# schematic.net
KiCad netlist of a schematic drawn in Altium Designer
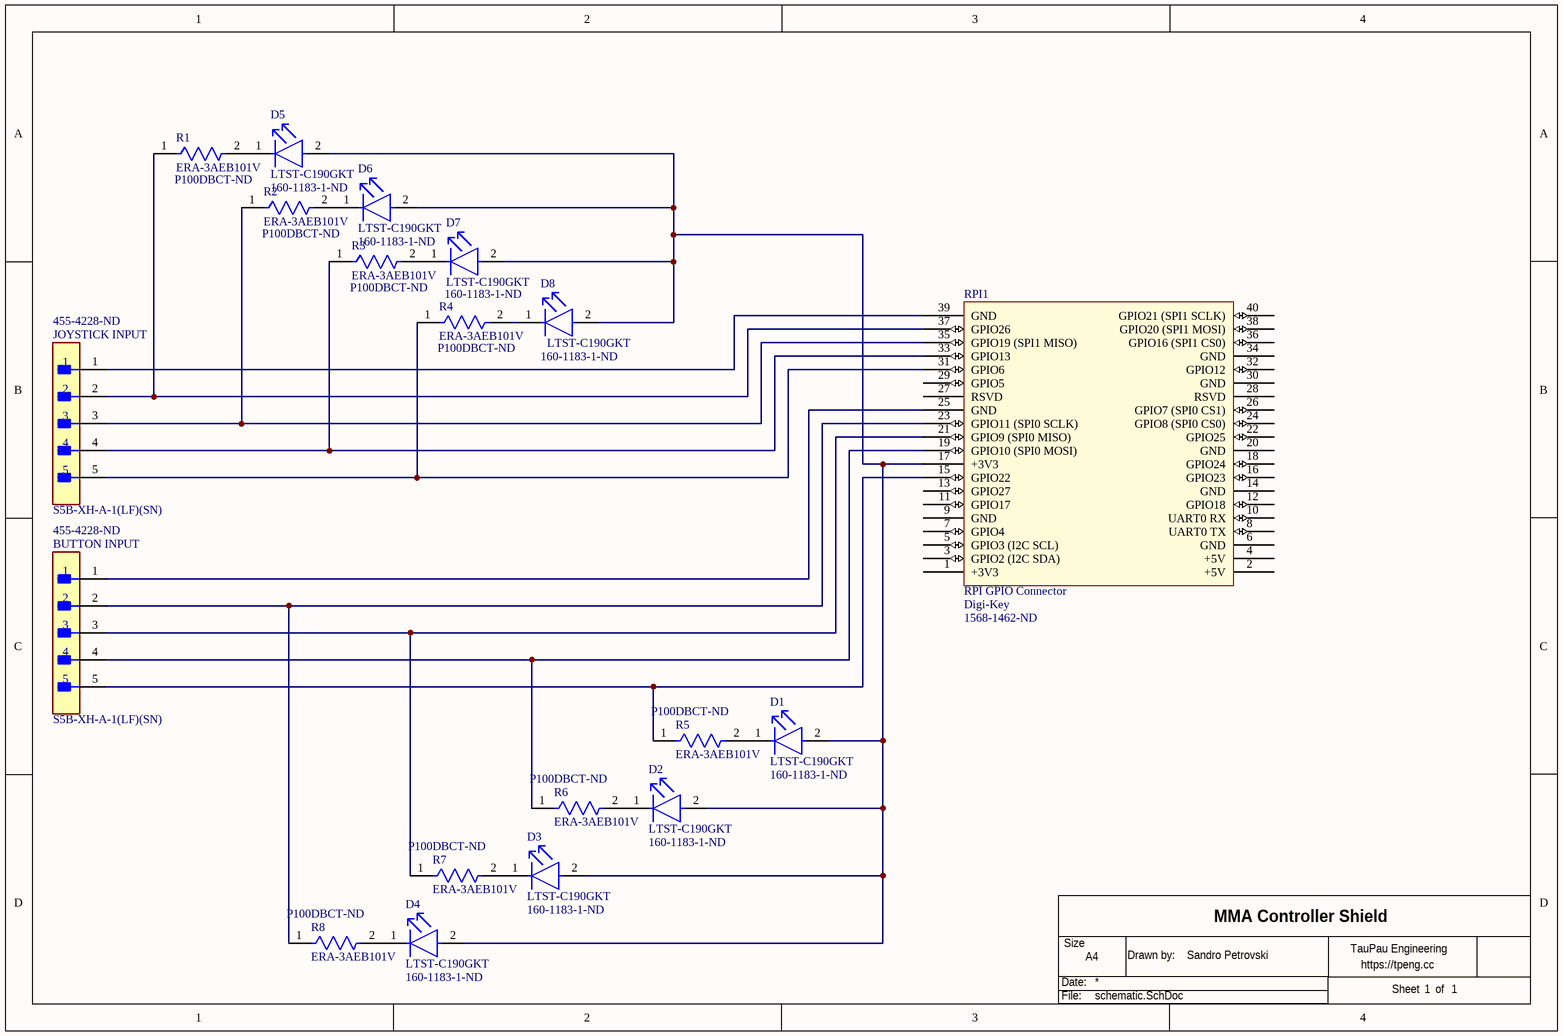
[diagram p0: schematic.SchDoc]

(export (version "E")
  (design (tool "Eeschema 10.0.6"))
  (components
    (comp (ref "*")
      (value "TPE Title Block")
      (description "TPE Title block")
      (libsource (lib "title_block") (part "TPE Title Block"))
    )
    (comp (ref "BUTTON INPUT")
      (value "S5B-XH-A-1(LF)(SN)")
      (footprint "FP-S5B-XH-A-1_LF_SN-MFG")
      (description "CONN HEADER R/A 5POS 2.5MM")
      (fields (field (name "SUPPLIER PART NUMBER 1") "455-4228-ND") (field (name "MANUFACTURER") "JST"))
      (libsource (lib "Altium Content Vault") (part "bf93c07fd2649a848d0ec8585582aab"))
    )
    (comp (ref "D1")
      (value "LTST-C190GKT")
      (footprint "FP-LTST-C190GKT-MFG")
      (description "LED GREEN CLEAR CHIP SMD")
      (fields
        (field (name "VOLTAGE") "2V")
        (field (name "SUPPLIER PART NUMBER 1") "160-1183-1-ND")
        (field (name "MANUFACTURER") "Vishay Lite-On")
      )
      (libsource (lib "Altium Content Vault") (part "8706943c75ba83719d021d2fdc84c58"))
    )
    (comp (ref "D2")
      (value "LTST-C190GKT")
      (footprint "FP-LTST-C190GKT-MFG")
      (description "LED GREEN CLEAR CHIP SMD")
      (fields
        (field (name "VOLTAGE") "2V")
        (field (name "SUPPLIER PART NUMBER 1") "160-1183-1-ND")
        (field (name "MANUFACTURER") "Vishay Lite-On")
      )
      (libsource (lib "Altium Content Vault") (part "8706943c75ba83719d021d2fdc84c58"))
    )
    (comp (ref "D3")
      (value "LTST-C190GKT")
      (footprint "FP-LTST-C190GKT-MFG")
      (description "LED GREEN CLEAR CHIP SMD")
      (fields
        (field (name "VOLTAGE") "2V")
        (field (name "SUPPLIER PART NUMBER 1") "160-1183-1-ND")
        (field (name "MANUFACTURER") "Vishay Lite-On")
      )
      (libsource (lib "Altium Content Vault") (part "8706943c75ba83719d021d2fdc84c58"))
    )
    (comp (ref "D4")
      (value "LTST-C190GKT")
      (footprint "FP-LTST-C190GKT-MFG")
      (description "LED GREEN CLEAR CHIP SMD")
      (fields
        (field (name "VOLTAGE") "2V")
        (field (name "SUPPLIER PART NUMBER 1") "160-1183-1-ND")
        (field (name "MANUFACTURER") "Vishay Lite-On")
      )
      (libsource (lib "Altium Content Vault") (part "8706943c75ba83719d021d2fdc84c58"))
    )
    (comp (ref "D5")
      (value "LTST-C190GKT")
      (footprint "FP-LTST-C190GKT-MFG")
      (description "LED GREEN CLEAR CHIP SMD")
      (fields
        (field (name "VOLTAGE") "2V")
        (field (name "SUPPLIER PART NUMBER 1") "160-1183-1-ND")
        (field (name "MANUFACTURER") "Vishay Lite-On")
      )
      (libsource (lib "Altium Content Vault") (part "8706943c75ba83719d021d2fdc84c58"))
    )
    (comp (ref "D6")
      (value "LTST-C190GKT")
      (footprint "FP-LTST-C190GKT-MFG")
      (description "LED GREEN CLEAR CHIP SMD")
      (fields
        (field (name "VOLTAGE") "2V")
        (field (name "SUPPLIER PART NUMBER 1") "160-1183-1-ND")
        (field (name "MANUFACTURER") "Vishay Lite-On")
      )
      (libsource (lib "Altium Content Vault") (part "8706943c75ba83719d021d2fdc84c58"))
    )
    (comp (ref "D7")
      (value "LTST-C190GKT")
      (footprint "FP-LTST-C190GKT-MFG")
      (description "LED GREEN CLEAR CHIP SMD")
      (fields
        (field (name "VOLTAGE") "2V")
        (field (name "SUPPLIER PART NUMBER 1") "160-1183-1-ND")
        (field (name "MANUFACTURER") "Vishay Lite-On")
      )
      (libsource (lib "Altium Content Vault") (part "8706943c75ba83719d021d2fdc84c58"))
    )
    (comp (ref "D8")
      (value "LTST-C190GKT")
      (footprint "FP-LTST-C190GKT-MFG")
      (description "LED GREEN CLEAR CHIP SMD")
      (fields
        (field (name "VOLTAGE") "2V")
        (field (name "SUPPLIER PART NUMBER 1") "160-1183-1-ND")
        (field (name "MANUFACTURER") "Vishay Lite-On")
      )
      (libsource (lib "Altium Content Vault") (part "8706943c75ba83719d021d2fdc84c58"))
    )
    (comp (ref "JOYSTICK INPUT")
      (value "S5B-XH-A-1(LF)(SN)")
      (footprint "FP-S5B-XH-A-1_LF_SN-MFG")
      (description "CONN HEADER R/A 5POS 2.5MM")
      (fields (field (name "SUPPLIER PART NUMBER 1") "455-4228-ND") (field (name "MANUFACTURER") "JST"))
      (libsource (lib "Altium Content Vault") (part "bf93c07fd2649a848d0ec8585582aab"))
    )
    (comp (ref "R1")
      (value "ERA-3AEB101V")
      (footprint "FP-ERA3A-IPC_B")
      (description "RES SMD 100 OHM 0.1% 1/10W 0603")
      (fields
        (field (name "TOLERANCE") "0.1%")
        (field (name "SUPPLIER PART NUMBER 1") "P100DBCT-ND")
        (field (name "MANUFACTURER") "Panasonic")
      )
      (libsource (lib "Altium Content Vault") (part "1029c3af85768c4190bb7ad29bc67b5"))
    )
    (comp (ref "R2")
      (value "ERA-3AEB101V")
      (footprint "FP-ERA3A-IPC_B")
      (description "RES SMD 100 OHM 0.1% 1/10W 0603")
      (fields
        (field (name "TOLERANCE") "0.1%")
        (field (name "SUPPLIER PART NUMBER 1") "P100DBCT-ND")
        (field (name "MANUFACTURER") "Panasonic")
      )
      (libsource (lib "Altium Content Vault") (part "1029c3af85768c4190bb7ad29bc67b5"))
    )
    (comp (ref "R3")
      (value "ERA-3AEB101V")
      (footprint "FP-ERA3A-IPC_B")
      (description "RES SMD 100 OHM 0.1% 1/10W 0603")
      (fields
        (field (name "TOLERANCE") "0.1%")
        (field (name "SUPPLIER PART NUMBER 1") "P100DBCT-ND")
        (field (name "MANUFACTURER") "Panasonic")
      )
      (libsource (lib "Altium Content Vault") (part "1029c3af85768c4190bb7ad29bc67b5"))
    )
    (comp (ref "R4")
      (value "ERA-3AEB101V")
      (footprint "FP-ERA3A-IPC_B")
      (description "RES SMD 100 OHM 0.1% 1/10W 0603")
      (fields
        (field (name "TOLERANCE") "0.1%")
        (field (name "SUPPLIER PART NUMBER 1") "P100DBCT-ND")
        (field (name "MANUFACTURER") "Panasonic")
      )
      (libsource (lib "Altium Content Vault") (part "1029c3af85768c4190bb7ad29bc67b5"))
    )
    (comp (ref "R5")
      (value "ERA-3AEB101V")
      (footprint "FP-ERA3A-IPC_B")
      (description "RES SMD 100 OHM 0.1% 1/10W 0603")
      (fields
        (field (name "TOLERANCE") "0.1%")
        (field (name "SUPPLIER PART NUMBER 1") "P100DBCT-ND")
        (field (name "MANUFACTURER") "Panasonic")
      )
      (libsource (lib "Altium Content Vault") (part "1029c3af85768c4190bb7ad29bc67b5"))
    )
    (comp (ref "R6")
      (value "ERA-3AEB101V")
      (footprint "FP-ERA3A-IPC_B")
      (description "RES SMD 100 OHM 0.1% 1/10W 0603")
      (fields
        (field (name "TOLERANCE") "0.1%")
        (field (name "SUPPLIER PART NUMBER 1") "P100DBCT-ND")
        (field (name "MANUFACTURER") "Panasonic")
      )
      (libsource (lib "Altium Content Vault") (part "1029c3af85768c4190bb7ad29bc67b5"))
    )
    (comp (ref "R7")
      (value "ERA-3AEB101V")
      (footprint "FP-ERA3A-IPC_B")
      (description "RES SMD 100 OHM 0.1% 1/10W 0603")
      (fields
        (field (name "TOLERANCE") "0.1%")
        (field (name "SUPPLIER PART NUMBER 1") "P100DBCT-ND")
        (field (name "MANUFACTURER") "Panasonic")
      )
      (libsource (lib "Altium Content Vault") (part "1029c3af85768c4190bb7ad29bc67b5"))
    )
    (comp (ref "R8")
      (value "ERA-3AEB101V")
      (footprint "FP-ERA3A-IPC_B")
      (description "RES SMD 100 OHM 0.1% 1/10W 0603")
      (fields
        (field (name "TOLERANCE") "0.1%")
        (field (name "SUPPLIER PART NUMBER 1") "P100DBCT-ND")
        (field (name "MANUFACTURER") "Panasonic")
      )
      (libsource (lib "Altium Content Vault") (part "1029c3af85768c4190bb7ad29bc67b5"))
    )
    (comp (ref "RPI1")
      (value "RPI GPIO Connector")
      (footprint "rpi")
      (description "GPIO Header for Raspberry Pi A+/B+/Pi 2/Pi 3 - 2x20")
      (fields
        (field (name "MANUFACTURER") "SparkFun Electronics")
        (field (name "MANUFACTURER PART NUMBER") "PRT-14017")
        (field (name "SUPPLIER 1") "Digi-Key")
        (field (name "SUPPLIER PART NUMBER 1") "1568-1462-ND")
      )
      (libsource (lib "rpi") (part "rpi connector"))
    )
  )
  (nets
    (net (code "1") (name "Net-(BUTTON INPUT-Pad1)") (class "Default")
      (node (ref "BUTTON INPUT") (pin "1") (pinfunction "1_1") (pintype "passive"))
      (node (ref "RPI1") (pin "25") (pinfunction "GND_25") (pintype "power_in"))
    )
    (net (code "2") (name "Net-(D1-A)") (class "Default")
      (node (ref "D1") (pin "2") (pinfunction "A_2") (pintype "passive"))
      (node (ref "D2") (pin "2") (pinfunction "A_2") (pintype "passive"))
      (node (ref "D3") (pin "2") (pinfunction "A_2") (pintype "passive"))
      (node (ref "D4") (pin "2") (pinfunction "A_2") (pintype "passive"))
      (node (ref "D5") (pin "2") (pinfunction "A_2") (pintype "passive"))
      (node (ref "D6") (pin "2") (pinfunction "A_2") (pintype "passive"))
      (node (ref "D7") (pin "2") (pinfunction "A_2") (pintype "passive"))
      (node (ref "D8") (pin "2") (pinfunction "A_2") (pintype "passive"))
      (node (ref "RPI1") (pin "17") (pinfunction "+3V3_17") (pintype "power_in"))
    )
    (net (code "3") (name "Net-(D1-C)") (class "Default")
      (node (ref "D1") (pin "1") (pinfunction "C_1") (pintype "passive"))
      (node (ref "R5") (pin "2") (pinfunction "2_2") (pintype "passive"))
    )
    (net (code "4") (name "Net-(D2-C)") (class "Default")
      (node (ref "D2") (pin "1") (pinfunction "C_1") (pintype "passive"))
      (node (ref "R6") (pin "2") (pinfunction "2_2") (pintype "passive"))
    )
    (net (code "5") (name "Net-(D3-C)") (class "Default")
      (node (ref "D3") (pin "1") (pinfunction "C_1") (pintype "passive"))
      (node (ref "R7") (pin "2") (pinfunction "2_2") (pintype "passive"))
    )
    (net (code "6") (name "Net-(D4-C)") (class "Default")
      (node (ref "D4") (pin "1") (pinfunction "C_1") (pintype "passive"))
      (node (ref "R8") (pin "2") (pinfunction "2_2") (pintype "passive"))
    )
    (net (code "7") (name "Net-(D5-C)") (class "Default")
      (node (ref "D5") (pin "1") (pinfunction "C_1") (pintype "passive"))
      (node (ref "R1") (pin "2") (pinfunction "2_2") (pintype "passive"))
    )
    (net (code "8") (name "Net-(D6-C)") (class "Default")
      (node (ref "D6") (pin "1") (pinfunction "C_1") (pintype "passive"))
      (node (ref "R2") (pin "2") (pinfunction "2_2") (pintype "passive"))
    )
    (net (code "9") (name "Net-(D7-C)") (class "Default")
      (node (ref "D7") (pin "1") (pinfunction "C_1") (pintype "passive"))
      (node (ref "R3") (pin "2") (pinfunction "2_2") (pintype "passive"))
    )
    (net (code "10") (name "Net-(D8-C)") (class "Default")
      (node (ref "D8") (pin "1") (pinfunction "C_1") (pintype "passive"))
      (node (ref "R4") (pin "2") (pinfunction "2_2") (pintype "passive"))
    )
    (net (code "11") (name "Net-(JOYSTICK INPUT-Pad1)") (class "Default")
      (node (ref "JOYSTICK INPUT") (pin "1") (pinfunction "1_1") (pintype "passive"))
      (node (ref "RPI1") (pin "39") (pinfunction "GND_39") (pintype "power_in"))
    )
    (net (code "12") (name "Net-(RPI1-GPIO6)") (class "Default")
      (node (ref "JOYSTICK INPUT") (pin "5") (pinfunction "5_5") (pintype "passive"))
      (node (ref "R4") (pin "1") (pinfunction "1_1") (pintype "passive"))
      (node (ref "RPI1") (pin "31") (pinfunction "GPIO6_31") (pintype "bidirectional"))
    )
    (net (code "13") (name "Net-(RPI1-GPIO9_(SPI0_MISO))") (class "Default")
      (node (ref "BUTTON INPUT") (pin "3") (pinfunction "3_3") (pintype "passive"))
      (node (ref "R7") (pin "1") (pinfunction "1_1") (pintype "passive"))
      (node (ref "RPI1") (pin "21") (pinfunction "GPIO9_(SPI0_MISO)_21") (pintype "bidirectional"))
    )
    (net (code "14") (name "Net-(RPI1-GPIO10_(SPI0_MOSI))") (class "Default")
      (node (ref "BUTTON INPUT") (pin "4") (pinfunction "4_4") (pintype "passive"))
      (node (ref "R6") (pin "1") (pinfunction "1_1") (pintype "passive"))
      (node (ref "RPI1") (pin "19") (pinfunction "GPIO10_(SPI0_MOSI)_19") (pintype "bidirectional"))
    )
    (net (code "15") (name "Net-(RPI1-GPIO11_(SPI0_SCLK))") (class "Default")
      (node (ref "BUTTON INPUT") (pin "2") (pinfunction "2_2") (pintype "passive"))
      (node (ref "R8") (pin "1") (pinfunction "1_1") (pintype "passive"))
      (node (ref "RPI1") (pin "23") (pinfunction "GPIO11_(SPI0_SCLK)_23") (pintype "bidirectional"))
    )
    (net (code "16") (name "Net-(RPI1-GPIO13)") (class "Default")
      (node (ref "JOYSTICK INPUT") (pin "4") (pinfunction "4_4") (pintype "passive"))
      (node (ref "R3") (pin "1") (pinfunction "1_1") (pintype "passive"))
      (node (ref "RPI1") (pin "33") (pinfunction "GPIO13_33") (pintype "bidirectional"))
    )
    (net (code "17") (name "Net-(RPI1-GPIO19_(SPI1_MISO))") (class "Default")
      (node (ref "JOYSTICK INPUT") (pin "3") (pinfunction "3_3") (pintype "passive"))
      (node (ref "R2") (pin "1") (pinfunction "1_1") (pintype "passive"))
      (node (ref "RPI1") (pin "35") (pinfunction "GPIO19_(SPI1_MISO)_35") (pintype "bidirectional"))
    )
    (net (code "18") (name "Net-(RPI1-GPIO22)") (class "Default")
      (node (ref "BUTTON INPUT") (pin "5") (pinfunction "5_5") (pintype "passive"))
      (node (ref "R5") (pin "1") (pinfunction "1_1") (pintype "passive"))
      (node (ref "RPI1") (pin "15") (pinfunction "GPIO22_15") (pintype "bidirectional"))
    )
    (net (code "19") (name "Net-(RPI1-GPIO26)") (class "Default")
      (node (ref "JOYSTICK INPUT") (pin "2") (pinfunction "2_2") (pintype "passive"))
      (node (ref "R1") (pin "1") (pinfunction "1_1") (pintype "passive"))
      (node (ref "RPI1") (pin "37") (pinfunction "GPIO26_37") (pintype "bidirectional"))
    )
    (net (code "20") (name "unconnected-(RPI1-+3V3-Pad1)") (class "Default")
      (node (ref "RPI1") (pin "1") (pinfunction "+3V3_1") (pintype "power_in"))
    )
    (net (code "21") (name "unconnected-(RPI1-+5V-Pad2)") (class "Default")
      (node (ref "RPI1") (pin "2") (pinfunction "+5V_2") (pintype "power_in"))
    )
    (net (code "22") (name "unconnected-(RPI1-+5V-Pad4)") (class "Default")
      (node (ref "RPI1") (pin "4") (pinfunction "+5V_4") (pintype "power_in"))
    )
    (net (code "23") (name "unconnected-(RPI1-GND-Pad6)") (class "Default")
      (node (ref "RPI1") (pin "6") (pinfunction "GND_6") (pintype "power_in"))
    )
    (net (code "24") (name "unconnected-(RPI1-GND-Pad9)") (class "Default")
      (node (ref "RPI1") (pin "9") (pinfunction "GND_9") (pintype "power_in"))
    )
    (net (code "25") (name "unconnected-(RPI1-GND-Pad14)") (class "Default")
      (node (ref "RPI1") (pin "14") (pinfunction "GND_14") (pintype "power_in"))
    )
    (net (code "26") (name "unconnected-(RPI1-GND-Pad20)") (class "Default")
      (node (ref "RPI1") (pin "20") (pinfunction "GND_20") (pintype "power_in"))
    )
    (net (code "27") (name "unconnected-(RPI1-GND-Pad30)") (class "Default")
      (node (ref "RPI1") (pin "30") (pinfunction "GND_30") (pintype "power_in"))
    )
    (net (code "28") (name "unconnected-(RPI1-GND-Pad34)") (class "Default")
      (node (ref "RPI1") (pin "34") (pinfunction "GND_34") (pintype "passive"))
    )
    (net (code "29") (name "unconnected-(RPI1-GPIO2_(I2C_SDA)-Pad3)") (class "Default")
      (node (ref "RPI1") (pin "3") (pinfunction "GPIO2_(I2C_SDA)_3") (pintype "bidirectional"))
    )
    (net (code "30") (name "unconnected-(RPI1-GPIO3_(I2C_SCL)-Pad5)") (class "Default")
      (node (ref "RPI1") (pin "5") (pinfunction "GPIO3_(I2C_SCL)_5") (pintype "bidirectional"))
    )
    (net (code "31") (name "unconnected-(RPI1-GPIO4-Pad7)") (class "Default")
      (node (ref "RPI1") (pin "7") (pinfunction "GPIO4_7") (pintype "bidirectional"))
    )
    (net (code "32") (name "unconnected-(RPI1-GPIO5-Pad29)") (class "Default")
      (node (ref "RPI1") (pin "29") (pinfunction "GPIO5_29") (pintype "bidirectional"))
    )
    (net (code "33") (name "unconnected-(RPI1-GPIO7_(SPI0_CS1)-Pad26)") (class "Default")
      (node (ref "RPI1") (pin "26") (pinfunction "GPIO7_(SPI0_CS1)_26") (pintype "bidirectional"))
    )
    (net (code "34") (name "unconnected-(RPI1-GPIO8_(SPI0_CS0)-Pad24)") (class "Default")
      (node (ref "RPI1") (pin "24") (pinfunction "GPIO8_(SPI0_CS0)_24") (pintype "bidirectional"))
    )
    (net (code "35") (name "unconnected-(RPI1-GPIO12-Pad32)") (class "Default")
      (node (ref "RPI1") (pin "32") (pinfunction "GPIO12_32") (pintype "bidirectional"))
    )
    (net (code "36") (name "unconnected-(RPI1-GPIO16_(SPI1_CS0)-Pad36)") (class "Default")
      (node (ref "RPI1") (pin "36") (pinfunction "GPIO16_(SPI1_CS0)_36") (pintype "bidirectional"))
    )
    (net (code "37") (name "unconnected-(RPI1-GPIO17-Pad11)") (class "Default")
      (node (ref "RPI1") (pin "11") (pinfunction "GPIO17_11") (pintype "bidirectional"))
    )
    (net (code "38") (name "unconnected-(RPI1-GPIO18-Pad12)") (class "Default")
      (node (ref "RPI1") (pin "12") (pinfunction "GPIO18_12") (pintype "bidirectional"))
    )
    (net (code "39") (name "unconnected-(RPI1-GPIO20_(SPI1_MOSI)-Pad38)") (class "Default")
      (node (ref "RPI1") (pin "38") (pinfunction "GPIO20_(SPI1_MOSI)_38") (pintype "bidirectional"))
    )
    (net (code "40") (name "unconnected-(RPI1-GPIO21_(SPI1_SCLK)-Pad40)") (class "Default")
      (node (ref "RPI1") (pin "40") (pinfunction "GPIO21_(SPI1_SCLK)_40") (pintype "bidirectional"))
    )
    (net (code "41") (name "unconnected-(RPI1-GPIO23-Pad16)") (class "Default")
      (node (ref "RPI1") (pin "16") (pinfunction "GPIO23_16") (pintype "bidirectional"))
    )
    (net (code "42") (name "unconnected-(RPI1-GPIO24-Pad18)") (class "Default")
      (node (ref "RPI1") (pin "18") (pinfunction "GPIO24_18") (pintype "bidirectional"))
    )
    (net (code "43") (name "unconnected-(RPI1-GPIO25-Pad22)") (class "Default")
      (node (ref "RPI1") (pin "22") (pinfunction "GPIO25_22") (pintype "bidirectional"))
    )
    (net (code "44") (name "unconnected-(RPI1-GPIO27-Pad13)") (class "Default")
      (node (ref "RPI1") (pin "13") (pinfunction "GPIO27_13") (pintype "bidirectional"))
    )
    (net (code "45") (name "unconnected-(RPI1-RSVD-Pad27)") (class "Default")
      (node (ref "RPI1") (pin "27") (pinfunction "RSVD_27") (pintype "passive"))
    )
    (net (code "46") (name "unconnected-(RPI1-RSVD-Pad28)") (class "Default")
      (node (ref "RPI1") (pin "28") (pinfunction "RSVD_28") (pintype "passive"))
    )
    (net (code "47") (name "unconnected-(RPI1-UART0_RX-Pad10)") (class "Default")
      (node (ref "RPI1") (pin "10") (pinfunction "UART0_RX_10") (pintype "bidirectional"))
    )
    (net (code "48") (name "unconnected-(RPI1-UART0_TX-Pad8)") (class "Default")
      (node (ref "RPI1") (pin "8") (pinfunction "UART0_TX_8") (pintype "bidirectional"))
    )
  )
)
